# powersupply.net
KiCad netlist of a schematic drawn in Altium Designer
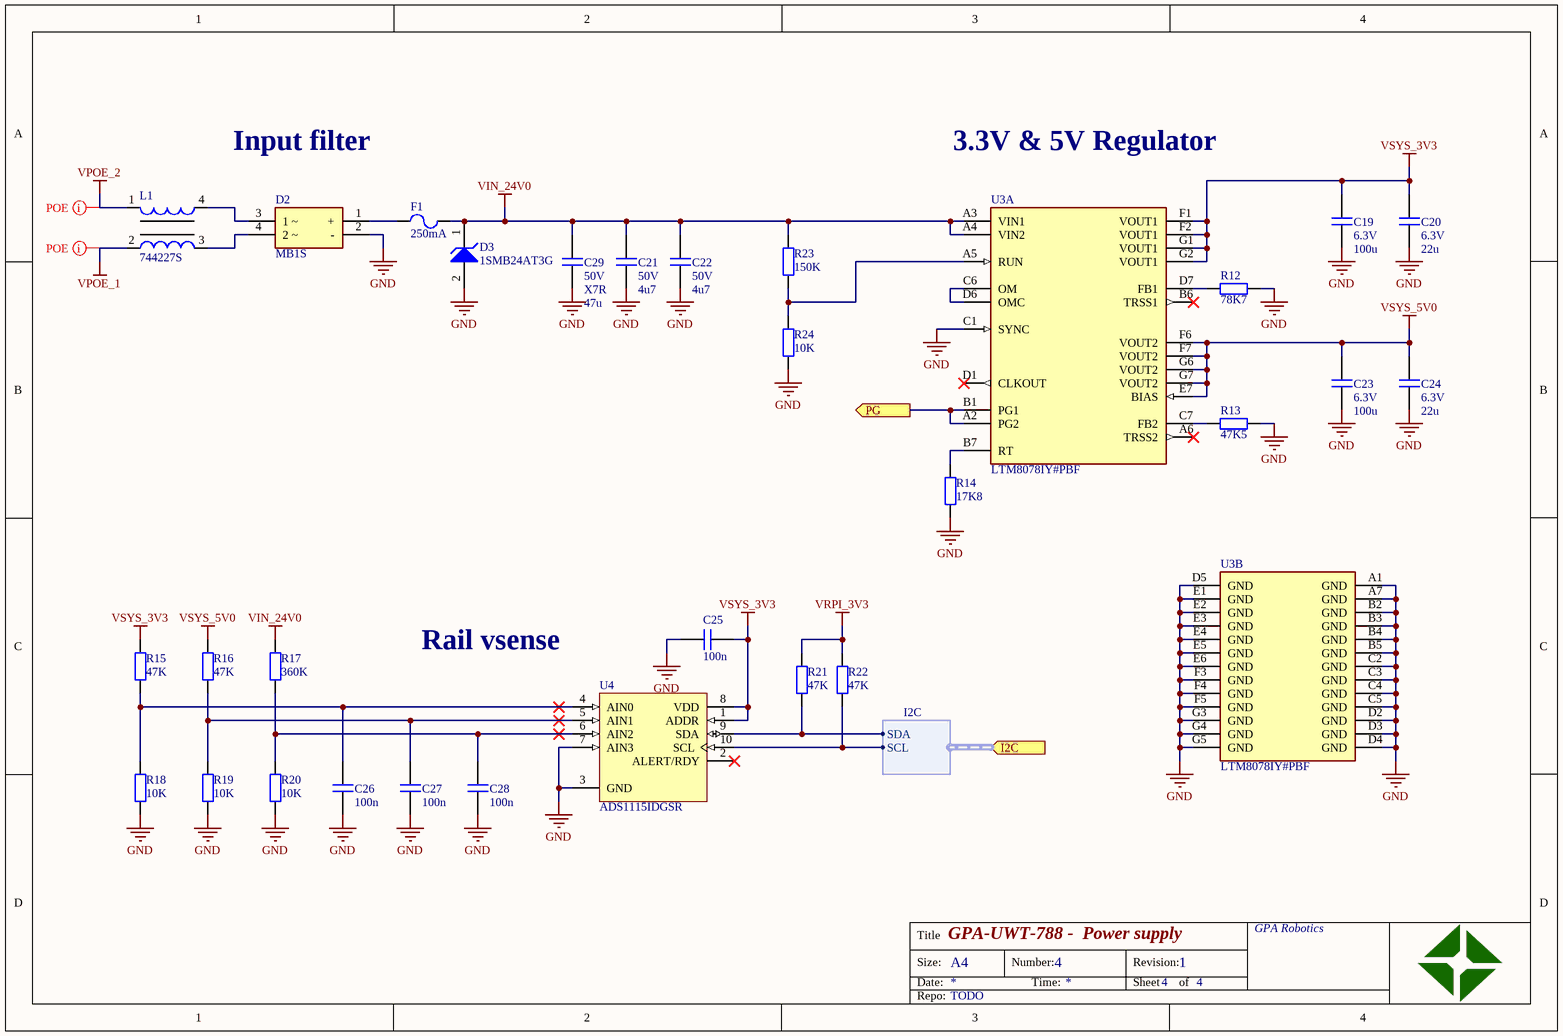
[diagram p0: powersupply.SchDoc]

(export (version "E")
  (design (tool "Eeschema 10.0.6"))
  (components
    (comp (ref "C19")
      (value "100u")
      (footprint "CAPC2012X11N")
      (description "Capacitor")
      (fields (field (name "VOLTAGE") "6.3V") (field (name "Comment") "cap"))
      (libsource (lib "lib_passives") (part "cap"))
    )
    (comp (ref "C20")
      (value "22u")
      (footprint "CAPC2012X11N")
      (description "Capacitor")
      (fields (field (name "VOLTAGE") "6.3V") (field (name "Comment") "cap"))
      (libsource (lib "lib_passives") (part "cap"))
    )
    (comp (ref "C21")
      (value "4u7")
      (footprint "CAPC2012X11N")
      (description "Capacitor")
      (fields (field (name "VOLTAGE") "50V") (field (name "Comment") "cap"))
      (libsource (lib "lib_passives") (part "cap"))
    )
    (comp (ref "C22")
      (value "4u7")
      (footprint "CAPC2012X11N")
      (description "Capacitor")
      (fields (field (name "VOLTAGE") "50V") (field (name "Comment") "cap"))
      (libsource (lib "lib_passives") (part "cap"))
    )
    (comp (ref "C23")
      (value "100u")
      (footprint "CAPC2012X11N")
      (description "Capacitor")
      (fields (field (name "VOLTAGE") "6.3V") (field (name "Comment") "cap"))
      (libsource (lib "lib_passives") (part "cap"))
    )
    (comp (ref "C24")
      (value "22u")
      (footprint "CAPC2012X11N")
      (description "Capacitor")
      (fields (field (name "VOLTAGE") "6.3V") (field (name "Comment") "cap"))
      (libsource (lib "lib_passives") (part "cap"))
    )
    (comp (ref "C25")
      (value "100n")
      (footprint "CAPC1005X06N")
      (description "Capacitor")
      (fields (field (name "Comment") "cap"))
      (libsource (lib "lib_passives") (part "cap"))
    )
    (comp (ref "C26")
      (value "100n")
      (footprint "CAPC1005X06N")
      (description "Capacitor")
      (fields (field (name "Comment") "cap"))
      (libsource (lib "lib_passives") (part "cap"))
    )
    (comp (ref "C27")
      (value "100n")
      (footprint "CAPC1005X06N")
      (description "Capacitor")
      (fields (field (name "Comment") "cap"))
      (libsource (lib "lib_passives") (part "cap"))
    )
    (comp (ref "C28")
      (value "100n")
      (footprint "CAPC1005X06N")
      (description "Capacitor")
      (fields (field (name "Comment") "cap"))
      (libsource (lib "lib_passives") (part "cap"))
    )
    (comp (ref "C29")
      (value "47u")
      (footprint "CAPC3225X14N")
      (description "Capacitor")
      (fields (field (name "VOLTAGE") "50V") (field (name "TYPE") "X7R") (field (name "Comment") "cap"))
      (libsource (lib "lib_passives") (part "cap"))
    )
    (comp (ref "D2")
      (value "MB1S")
      (footprint "FP-751EP-MFG")
      (description "BRIDGE RECT 1P 100V 500MA 4SOIC")
      (fields
        (field (name "MANUFACTURER") "ON Semiconductor")
        (field (name "OCTOPART") "https://octopart.com/mb1s-on+semiconductor-84329760")
      )
      (libsource (lib "Altium Content Vault") (part "3aa94783aa439bc10c895aae2b3e5ec"))
    )
    (comp (ref "D3")
      (value "1SMB24AT3G")
      (footprint "ONSC-SMB-2-403A-03_H_V")
      (fields (field (name "MANUFACTURER") "On Semiconductor"))
      (libsource (lib "Altium Content Vault") (part "ONSC-K1A2-2"))
    )
    (comp (ref "F1")
      (value "250mA")
      (footprint "RESC1608X06N")
      (description "Resistor")
      (fields (field (name "Comment") "fuse"))
      (libsource (lib "lib_passives") (part "fuse"))
    )
    (comp (ref "L1")
      (value "744227S")
      (footprint "WE-SL2")
      (description "SMD Common Mode Line Filter WE-SL2, L = 51.0 µH")
      (libsource (lib "Altium Content Vault") (part "PAS-IND-INDUCTOR-4C"))
    )
    (comp (ref "R12")
      (value "78K7")
      (footprint "RESC1005X04N")
      (description "Resistor")
      (fields (field (name "Comment") "res"))
      (libsource (lib "") (part "res_1"))
    )
    (comp (ref "R13")
      (value "47K5")
      (footprint "RESC1005X04N")
      (description "Resistor")
      (fields (field (name "Comment") "res"))
      (libsource (lib "") (part "res_1"))
    )
    (comp (ref "R14")
      (value "17K8")
      (footprint "RESC1005X04N")
      (description "Resistor")
      (fields (field (name "Comment") "res"))
      (libsource (lib "lib_passives") (part "res"))
    )
    (comp (ref "R15")
      (value "47K")
      (footprint "RESC1005X04N")
      (description "Resistor")
      (fields (field (name "Comment") "res"))
      (libsource (lib "lib_passives") (part "res"))
    )
    (comp (ref "R16")
      (value "47K")
      (footprint "RESC1005X04N")
      (description "Resistor")
      (fields (field (name "Comment") "res"))
      (libsource (lib "lib_passives") (part "res"))
    )
    (comp (ref "R17")
      (value "360K")
      (footprint "RESC1005X04N")
      (description "Resistor")
      (fields (field (name "Comment") "res"))
      (libsource (lib "lib_passives") (part "res"))
    )
    (comp (ref "R18")
      (value "10K")
      (footprint "RESC1005X04N")
      (description "Resistor")
      (fields (field (name "Comment") "res"))
      (libsource (lib "lib_passives") (part "res"))
    )
    (comp (ref "R19")
      (value "10K")
      (footprint "RESC1005X04N")
      (description "Resistor")
      (fields (field (name "Comment") "res"))
      (libsource (lib "lib_passives") (part "res"))
    )
    (comp (ref "R20")
      (value "10K")
      (footprint "RESC1005X04N")
      (description "Resistor")
      (fields (field (name "Comment") "res"))
      (libsource (lib "lib_passives") (part "res"))
    )
    (comp (ref "R21")
      (value "47K")
      (footprint "RESC1005X04N")
      (description "Resistor")
      (fields (field (name "Comment") "res"))
      (libsource (lib "lib_passives") (part "res"))
    )
    (comp (ref "R22")
      (value "47K")
      (footprint "RESC1005X04N")
      (description "Resistor")
      (fields (field (name "Comment") "res"))
      (libsource (lib "lib_passives") (part "res"))
    )
    (comp (ref "R23")
      (value "150K")
      (footprint "RESC1005X04N")
      (description "Resistor")
      (fields (field (name "Comment") "res"))
      (libsource (lib "lib_passives") (part "res"))
    )
    (comp (ref "R24")
      (value "10K")
      (footprint "RESC1005X04N")
      (description "Resistor")
      (fields (field (name "Comment") "res"))
      (libsource (lib "lib_passives") (part "res"))
    )
    (comp (ref "U3")
      (value "LTM8078IY#PBF")
      (footprint "FP-BGA-49-05-08-1518-MFG")
      (description "DUAL 40VIN, 3A SILENT SWITCR UMO")
      (libsource (lib "Altium Content Vault") (part "de9a6fdfa50fe0a471f88eb8980317e"))
    )
    (comp (ref "U4")
      (value "ADS1115IDGSR")
      (footprint "TI-DGS10_N")
      (fields (field (name "MANUFACTURER") "Texas Instruments"))
      (libsource (lib "Altium Content Vault") (part "TI-ADS1015_1115-10"))
    )
  )
  (nets
    (net (code "2") (name "/PG") (class "Default")
      (node (ref "U3") (pin "A2") (pinfunction "PG2_A2") (pintype "open_collector"))
      (node (ref "U3") (pin "B1") (pinfunction "PG1_B1") (pintype "open_collector"))
    )
    (net (code "4") (name "GND") (class "Default")
      (node (ref "C19") (pin "1") (pinfunction "1_1") (pintype "passive"))
      (node (ref "C20") (pin "1") (pinfunction "1_1") (pintype "passive"))
      (node (ref "C21") (pin "1") (pinfunction "1_1") (pintype "passive"))
      (node (ref "C22") (pin "1") (pinfunction "1_1") (pintype "passive"))
      (node (ref "C23") (pin "1") (pinfunction "1_1") (pintype "passive"))
      (node (ref "C24") (pin "1") (pinfunction "1_1") (pintype "passive"))
      (node (ref "C25") (pin "1") (pinfunction "1_1") (pintype "passive"))
      (node (ref "C26") (pin "1") (pinfunction "1_1") (pintype "passive"))
      (node (ref "C27") (pin "1") (pinfunction "1_1") (pintype "passive"))
      (node (ref "C28") (pin "1") (pinfunction "1_1") (pintype "passive"))
      (node (ref "C29") (pin "1") (pinfunction "1_1") (pintype "passive"))
      (node (ref "D2") (pin "2") (pinfunction "-_2") (pintype "passive"))
      (node (ref "D3") (pin "2") (pinfunction "A_2") (pintype "passive"))
      (node (ref "R12") (pin "2") (pinfunction "2_2") (pintype "passive"))
      (node (ref "R13") (pin "2") (pinfunction "2_2") (pintype "passive"))
      (node (ref "R14") (pin "1") (pinfunction "1_1") (pintype "passive"))
      (node (ref "R18") (pin "1") (pinfunction "1_1") (pintype "passive"))
      (node (ref "R19") (pin "1") (pinfunction "1_1") (pintype "passive"))
      (node (ref "R20") (pin "1") (pinfunction "1_1") (pintype "passive"))
      (node (ref "R24") (pin "1") (pinfunction "1_1") (pintype "passive"))
      (node (ref "U3") (pin "A1") (pinfunction "GND_A1") (pintype "power_in"))
      (node (ref "U3") (pin "A7") (pinfunction "GND_A7") (pintype "power_in"))
      (node (ref "U3") (pin "B2") (pinfunction "GND_B2") (pintype "power_in"))
      (node (ref "U3") (pin "B3") (pinfunction "GND_B3") (pintype "power_in"))
      (node (ref "U3") (pin "B4") (pinfunction "GND_B4") (pintype "power_in"))
      (node (ref "U3") (pin "B5") (pinfunction "GND_B5") (pintype "power_in"))
      (node (ref "U3") (pin "C1") (pinfunction "SYNC_C1") (pintype "input"))
      (node (ref "U3") (pin "C2") (pinfunction "GND_C2") (pintype "power_in"))
      (node (ref "U3") (pin "C3") (pinfunction "GND_C3") (pintype "power_in"))
      (node (ref "U3") (pin "C4") (pinfunction "GND_C4") (pintype "power_in"))
      (node (ref "U3") (pin "C5") (pinfunction "GND_C5") (pintype "power_in"))
      (node (ref "U3") (pin "D2") (pinfunction "GND_D2") (pintype "power_in"))
      (node (ref "U3") (pin "D3") (pinfunction "GND_D3") (pintype "power_in"))
      (node (ref "U3") (pin "D4") (pinfunction "GND_D4") (pintype "power_in"))
      (node (ref "U3") (pin "D5") (pinfunction "GND_D5") (pintype "power_in"))
      (node (ref "U3") (pin "E1") (pinfunction "GND_E1") (pintype "power_in"))
      (node (ref "U3") (pin "E2") (pinfunction "GND_E2") (pintype "power_in"))
      (node (ref "U3") (pin "E3") (pinfunction "GND_E3") (pintype "power_in"))
      (node (ref "U3") (pin "E4") (pinfunction "GND_E4") (pintype "power_in"))
      (node (ref "U3") (pin "E5") (pinfunction "GND_E5") (pintype "power_in"))
      (node (ref "U3") (pin "E6") (pinfunction "GND_E6") (pintype "power_in"))
      (node (ref "U3") (pin "F3") (pinfunction "GND_F3") (pintype "power_in"))
      (node (ref "U3") (pin "F4") (pinfunction "GND_F4") (pintype "power_in"))
      (node (ref "U3") (pin "F5") (pinfunction "GND_F5") (pintype "power_in"))
      (node (ref "U3") (pin "G3") (pinfunction "GND_G3") (pintype "power_in"))
      (node (ref "U3") (pin "G4") (pinfunction "GND_G4") (pintype "power_in"))
      (node (ref "U3") (pin "G5") (pinfunction "GND_G5") (pintype "power_in"))
      (node (ref "U4") (pin "3") (pinfunction "GND_3") (pintype "power_in"))
      (node (ref "U4") (pin "7") (pinfunction "AIN3_7") (pintype "input"))
    )
    (net (code "5") (name "Net-(D2-+)") (class "Default")
      (node (ref "D2") (pin "1") (pinfunction "+_1") (pintype "passive"))
      (node (ref "F1") (pin "1") (pinfunction "1_1") (pintype "passive"))
    )
    (net (code "6") (name "Net-(D2-1_~)") (class "Default")
      (node (ref "D2") (pin "3") (pinfunction "1_~_3") (pintype "passive"))
      (node (ref "L1") (pin "4") (pinfunction "4_4") (pintype "passive"))
    )
    (net (code "7") (name "Net-(D2-2_~)") (class "Default")
      (node (ref "D2") (pin "4") (pinfunction "2_~_4") (pintype "passive"))
      (node (ref "L1") (pin "3") (pinfunction "3_3") (pintype "passive"))
    )
    (net (code "8") (name "Net-(U3A-FB1)") (class "Default")
      (node (ref "R12") (pin "1") (pinfunction "1_1") (pintype "passive"))
      (node (ref "U3") (pin "D7") (pinfunction "FB1_D7") (pintype "passive"))
    )
    (net (code "9") (name "Net-(U3A-FB2)") (class "Default")
      (node (ref "R13") (pin "1") (pinfunction "1_1") (pintype "passive"))
      (node (ref "U3") (pin "C7") (pinfunction "FB2_C7") (pintype "passive"))
    )
    (net (code "10") (name "Net-(U3A-OM)") (class "Default")
      (node (ref "U3") (pin "C6") (pinfunction "OM_C6") (pintype "passive"))
      (node (ref "U3") (pin "D6") (pinfunction "OMC_D6") (pintype "passive"))
    )
    (net (code "11") (name "Net-(U3A-RT)") (class "Default")
      (node (ref "R14") (pin "2") (pinfunction "2_2") (pintype "passive"))
      (node (ref "U3") (pin "B7") (pinfunction "RT_B7") (pintype "passive"))
    )
    (net (code "12") (name "Net-(U3A-RUN)") (class "Default")
      (node (ref "R23") (pin "1") (pinfunction "1_1") (pintype "passive"))
      (node (ref "R24") (pin "2") (pinfunction "2_2") (pintype "passive"))
      (node (ref "U3") (pin "A5") (pinfunction "RUN_A5") (pintype "input"))
    )
    (net (code "13") (name "Net-(U4-AIN0)") (class "Default")
      (node (ref "C26") (pin "2") (pinfunction "2_2") (pintype "passive"))
      (node (ref "R15") (pin "1") (pinfunction "1_1") (pintype "passive"))
      (node (ref "R18") (pin "2") (pinfunction "2_2") (pintype "passive"))
      (node (ref "U4") (pin "4") (pinfunction "AIN0_4") (pintype "input"))
    )
    (net (code "14") (name "Net-(U4-AIN1)") (class "Default")
      (node (ref "C27") (pin "2") (pinfunction "2_2") (pintype "passive"))
      (node (ref "R16") (pin "1") (pinfunction "1_1") (pintype "passive"))
      (node (ref "R19") (pin "2") (pinfunction "2_2") (pintype "passive"))
      (node (ref "U4") (pin "5") (pinfunction "AIN1_5") (pintype "input"))
    )
    (net (code "15") (name "Net-(U4-AIN2)") (class "Default")
      (node (ref "C28") (pin "2") (pinfunction "2_2") (pintype "passive"))
      (node (ref "R17") (pin "1") (pinfunction "1_1") (pintype "passive"))
      (node (ref "R20") (pin "2") (pinfunction "2_2") (pintype "passive"))
      (node (ref "U4") (pin "6") (pinfunction "AIN2_6") (pintype "input"))
    )
    (net (code "16") (name "Net-(U4-SCL)") (class "Default")
      (node (ref "R22") (pin "1") (pinfunction "1_1") (pintype "passive"))
      (node (ref "U4") (pin "10") (pinfunction "SCL_10") (pintype "input"))
    )
    (net (code "17") (name "Net-(U4-SDA)") (class "Default")
      (node (ref "R21") (pin "1") (pinfunction "1_1") (pintype "passive"))
      (node (ref "U4") (pin "9") (pinfunction "SDA_9") (pintype "bidirectional"))
    )
    (net (code "18") (name "VIN_24V0") (class "Default")
      (node (ref "C21") (pin "2") (pinfunction "2_2") (pintype "passive"))
      (node (ref "C22") (pin "2") (pinfunction "2_2") (pintype "passive"))
      (node (ref "C29") (pin "2") (pinfunction "2_2") (pintype "passive"))
      (node (ref "D3") (pin "1") (pinfunction "K_1") (pintype "passive"))
      (node (ref "F1") (pin "2") (pinfunction "2_2") (pintype "passive"))
      (node (ref "R17") (pin "2") (pinfunction "2_2") (pintype "passive"))
      (node (ref "R23") (pin "2") (pinfunction "2_2") (pintype "passive"))
      (node (ref "U3") (pin "A3") (pinfunction "VIN1_A3") (pintype "power_in"))
      (node (ref "U3") (pin "A4") (pinfunction "VIN2_A4") (pintype "power_in"))
    )
    (net (code "19") (name "VPOE_1") (class "Default")
      (node (ref "L1") (pin "2") (pinfunction "2_2") (pintype "passive"))
    )
    (net (code "20") (name "VPOE_2") (class "Default")
      (node (ref "L1") (pin "1") (pinfunction "1_1") (pintype "passive"))
    )
    (net (code "21") (name "VRPI_3V3") (class "Default")
      (node (ref "R21") (pin "2") (pinfunction "2_2") (pintype "passive"))
      (node (ref "R22") (pin "2") (pinfunction "2_2") (pintype "passive"))
    )
    (net (code "22") (name "VSYS_3V3") (class "Default")
      (node (ref "C19") (pin "2") (pinfunction "2_2") (pintype "passive"))
      (node (ref "C20") (pin "2") (pinfunction "2_2") (pintype "passive"))
      (node (ref "C25") (pin "2") (pinfunction "2_2") (pintype "passive"))
      (node (ref "R15") (pin "2") (pinfunction "2_2") (pintype "passive"))
      (node (ref "U3") (pin "F1") (pinfunction "VOUT1_F1") (pintype "power_in"))
      (node (ref "U3") (pin "F2") (pinfunction "VOUT1_F2") (pintype "power_in"))
      (node (ref "U3") (pin "G1") (pinfunction "VOUT1_G1") (pintype "power_in"))
      (node (ref "U3") (pin "G2") (pinfunction "VOUT1_G2") (pintype "power_in"))
      (node (ref "U4") (pin "1") (pinfunction "ADDR_1") (pintype "input"))
      (node (ref "U4") (pin "8") (pinfunction "VDD_8") (pintype "power_in"))
    )
    (net (code "23") (name "VSYS_5V0") (class "Default")
      (node (ref "C23") (pin "2") (pinfunction "2_2") (pintype "passive"))
      (node (ref "C24") (pin "2") (pinfunction "2_2") (pintype "passive"))
      (node (ref "R16") (pin "2") (pinfunction "2_2") (pintype "passive"))
      (node (ref "U3") (pin "E7") (pinfunction "BIAS_E7") (pintype "input"))
      (node (ref "U3") (pin "F6") (pinfunction "VOUT2_F6") (pintype "power_in"))
      (node (ref "U3") (pin "F7") (pinfunction "VOUT2_F7") (pintype "power_in"))
      (node (ref "U3") (pin "G6") (pinfunction "VOUT2_G6") (pintype "power_in"))
      (node (ref "U3") (pin "G7") (pinfunction "VOUT2_G7") (pintype "power_in"))
    )
    (net (code "24") (name "unconnected-(U3A-CLKOUT-PadD1)") (class "Default")
      (node (ref "U3") (pin "D1") (pinfunction "CLKOUT_D1") (pintype "output+no_connect"))
    )
    (net (code "25") (name "unconnected-(U3A-TRSS1-PadB6)") (class "Default")
      (node (ref "U3") (pin "B6") (pinfunction "TRSS1_B6") (pintype "output+no_connect"))
    )
    (net (code "26") (name "unconnected-(U3A-TRSS2-PadA6)") (class "Default")
      (node (ref "U3") (pin "A6") (pinfunction "TRSS2_A6") (pintype "output+no_connect"))
    )
    (net (code "27") (name "unconnected-(U4-ALERT{slash}RDY-Pad2)") (class "Default")
      (node (ref "U4") (pin "2") (pinfunction "ALERT/RDY_2") (pintype "open_collector+no_connect"))
    )
  )
)
